# LedDriverTest2.net
KiCad netlist of a schematic drawn in EAGLE
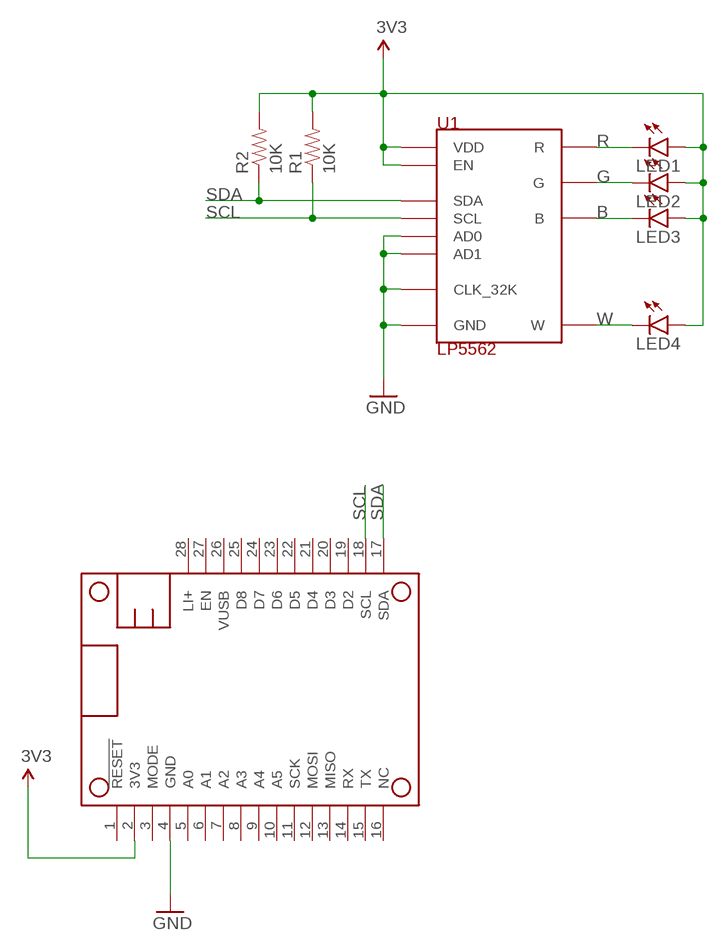
[diagram p0: schematic, sheet 1]

(export (version "E")
  (design (tool "Eeschema 10.0.6"))
  (components
    (comp (ref "LED1")
      (value "LED3MM")
      (footprint "eagle-import:LED3MM")
      (libsource (lib "eagle-import") (part "LED3MM"))
    )
    (comp (ref "LED2")
      (value "LED3MM")
      (footprint "eagle-import:LED3MM")
      (libsource (lib "eagle-import") (part "LED3MM"))
    )
    (comp (ref "LED3")
      (value "LED3MM")
      (footprint "eagle-import:LED3MM")
      (libsource (lib "eagle-import") (part "LED3MM"))
    )
    (comp (ref "LED4")
      (value "LED3MM")
      (footprint "eagle-import:LED3MM")
      (libsource (lib "eagle-import") (part "LED3MM"))
    )
    (comp (ref "MS1")
      (value "FEATHERWING_NODIM")
      (footprint "eagle-import:FEATHERWING_NODIM")
      (libsource (lib "eagle-import") (part "FEATHERWING_NODIM"))
    )
    (comp (ref "R1")
      (value "10K")
      (footprint "eagle-import:0603-RES")
      (libsource (lib "eagle-import") (part "RES-10K-06030603"))
    )
    (comp (ref "R2")
      (value "10K")
      (footprint "eagle-import:0603-RES")
      (libsource (lib "eagle-import") (part "RES-10K-06030603"))
    )
    (comp (ref "U1")
      (value "LP5562")
      (footprint "eagle-import:DSBGA12-TI")
      (libsource (lib "eagle-import") (part "LP5562-LED-DRIVER"))
    )
  )
  (nets
    (net (code "1") (name "/B") (class "Default")
      (node (ref "LED3") (pin "K") (pinfunction "C_K") (pintype "passive"))
      (node (ref "U1") (pin "A4") (pinfunction "B_A4") (pintype "open_collector"))
    )
    (net (code "2") (name "/G") (class "Default")
      (node (ref "LED2") (pin "K") (pinfunction "C_K") (pintype "passive"))
      (node (ref "U1") (pin "B4") (pinfunction "G_B4") (pintype "open_collector"))
    )
    (net (code "3") (name "/LI+") (class "Default")
      (node (ref "MS1") (pin "28") (pinfunction "LI+_28") (pintype "power_in"))
    )
    (net (code "4") (name "/R") (class "Default")
      (node (ref "LED1") (pin "K") (pinfunction "C_K") (pintype "passive"))
      (node (ref "U1") (pin "C4") (pinfunction "R_C4") (pintype "open_collector"))
    )
    (net (code "5") (name "/SCL") (class "Default")
      (node (ref "MS1") (pin "18") (pinfunction "SCL_18") (pintype "bidirectional"))
      (node (ref "R1") (pin "1") (pinfunction "1_1") (pintype "passive"))
      (node (ref "U1") (pin "C2") (pinfunction "SCL_C2") (pintype "input"))
    )
    (net (code "6") (name "/SDA") (class "Default")
      (node (ref "MS1") (pin "17") (pinfunction "SDA_17") (pintype "bidirectional"))
      (node (ref "R2") (pin "1") (pinfunction "1_1") (pintype "passive"))
      (node (ref "U1") (pin "C1") (pinfunction "SDA_C1") (pintype "bidirectional"))
    )
    (net (code "7") (name "/VUSB") (class "Default")
      (node (ref "MS1") (pin "26") (pinfunction "VUSB_26") (pintype "power_in"))
    )
    (net (code "8") (name "/W") (class "Default")
      (node (ref "LED4") (pin "K") (pinfunction "C_K") (pintype "passive"))
      (node (ref "U1") (pin "A1") (pinfunction "W_A1") (pintype "open_collector"))
    )
    (net (code "9") (name "3V3") (class "Default")
      (node (ref "LED1") (pin "A") (pinfunction "A_A") (pintype "passive"))
      (node (ref "LED2") (pin "A") (pinfunction "A_A") (pintype "passive"))
      (node (ref "LED3") (pin "A") (pinfunction "A_A") (pintype "passive"))
      (node (ref "LED4") (pin "A") (pinfunction "A_A") (pintype "passive"))
      (node (ref "MS1") (pin "2") (pinfunction "3V3_2") (pintype "power_in"))
      (node (ref "R1") (pin "2") (pinfunction "2_2") (pintype "passive"))
      (node (ref "R2") (pin "2") (pinfunction "2_2") (pintype "passive"))
      (node (ref "U1") (pin "A2") (pinfunction "VDD_A2") (pintype "power_in"))
      (node (ref "U1") (pin "C3") (pinfunction "EN_C3") (pintype "power_in"))
    )
    (net (code "10") (name "GND") (class "Default")
      (node (ref "MS1") (pin "4") (pinfunction "GND_4") (pintype "power_in"))
      (node (ref "U1") (pin "A3") (pinfunction "CLK_32K_A3") (pintype "input"))
      (node (ref "U1") (pin "B1") (pinfunction "AD1_B1") (pintype "input"))
      (node (ref "U1") (pin "B2") (pinfunction "AD0_B2") (pintype "input"))
      (node (ref "U1") (pin "B3") (pinfunction "GND_B3") (pintype "power_in"))
    )
    (net (code "11") (name "unconnected-(MS1-A0-Pad5)") (class "Default")
      (node (ref "MS1") (pin "5") (pinfunction "A0_5") (pintype "bidirectional"))
    )
    (net (code "12") (name "unconnected-(MS1-A1-Pad6)") (class "Default")
      (node (ref "MS1") (pin "6") (pinfunction "A1_6") (pintype "bidirectional"))
    )
    (net (code "13") (name "unconnected-(MS1-A2-Pad7)") (class "Default")
      (node (ref "MS1") (pin "7") (pinfunction "A2_7") (pintype "bidirectional"))
    )
    (net (code "14") (name "unconnected-(MS1-A3-Pad8)") (class "Default")
      (node (ref "MS1") (pin "8") (pinfunction "A3_8") (pintype "bidirectional"))
    )
    (net (code "15") (name "unconnected-(MS1-A4-Pad9)") (class "Default")
      (node (ref "MS1") (pin "9") (pinfunction "A4_9") (pintype "bidirectional"))
    )
    (net (code "16") (name "unconnected-(MS1-A5-Pad10)") (class "Default")
      (node (ref "MS1") (pin "10") (pinfunction "A5_10") (pintype "bidirectional"))
    )
    (net (code "17") (name "unconnected-(MS1-D2-Pad19)") (class "Default")
      (node (ref "MS1") (pin "19") (pinfunction "D2_19") (pintype "bidirectional"))
    )
    (net (code "18") (name "unconnected-(MS1-D3-Pad20)") (class "Default")
      (node (ref "MS1") (pin "20") (pinfunction "D3_20") (pintype "bidirectional"))
    )
    (net (code "19") (name "unconnected-(MS1-D4-Pad21)") (class "Default")
      (node (ref "MS1") (pin "21") (pinfunction "D4_21") (pintype "bidirectional"))
    )
    (net (code "20") (name "unconnected-(MS1-D5-Pad22)") (class "Default")
      (node (ref "MS1") (pin "22") (pinfunction "D5_22") (pintype "bidirectional"))
    )
    (net (code "21") (name "unconnected-(MS1-D6-Pad23)") (class "Default")
      (node (ref "MS1") (pin "23") (pinfunction "D6_23") (pintype "bidirectional"))
    )
    (net (code "22") (name "unconnected-(MS1-D7-Pad24)") (class "Default")
      (node (ref "MS1") (pin "24") (pinfunction "D7_24") (pintype "bidirectional"))
    )
    (net (code "23") (name "unconnected-(MS1-D8-Pad25)") (class "Default")
      (node (ref "MS1") (pin "25") (pinfunction "D8_25") (pintype "bidirectional"))
    )
    (net (code "24") (name "unconnected-(MS1-EN-Pad27)") (class "Default")
      (node (ref "MS1") (pin "27") (pinfunction "EN_27") (pintype "passive"))
    )
    (net (code "25") (name "unconnected-(MS1-MISO-Pad13)") (class "Default")
      (node (ref "MS1") (pin "13") (pinfunction "MISO_13") (pintype "bidirectional"))
    )
    (net (code "26") (name "unconnected-(MS1-MODE-Pad3)") (class "Default")
      (node (ref "MS1") (pin "3") (pinfunction "MODE_3") (pintype "passive"))
    )
    (net (code "27") (name "unconnected-(MS1-MOSI-Pad12)") (class "Default")
      (node (ref "MS1") (pin "12") (pinfunction "MOSI_12") (pintype "bidirectional"))
    )
    (net (code "28") (name "unconnected-(MS1-NC-Pad16)") (class "Default")
      (node (ref "MS1") (pin "16") (pinfunction "NC_16") (pintype "passive"))
    )
    (net (code "29") (name "unconnected-(MS1-RX-Pad14)") (class "Default")
      (node (ref "MS1") (pin "14") (pinfunction "RX_14") (pintype "bidirectional"))
    )
    (net (code "30") (name "unconnected-(MS1-SCK-Pad11)") (class "Default")
      (node (ref "MS1") (pin "11") (pinfunction "SCK_11") (pintype "bidirectional"))
    )
    (net (code "31") (name "unconnected-(MS1-TX-Pad15)") (class "Default")
      (node (ref "MS1") (pin "15") (pinfunction "TX_15") (pintype "bidirectional"))
    )
    (net (code "32") (name "unconnected-(MS1-~{RESET}-Pad1)") (class "Default")
      (node (ref "MS1") (pin "1") (pinfunction "~{RESET}_1") (pintype "input"))
    )
  )
)
